# ISO_Power.net
KiCad netlist of a schematic drawn in Altium Designer
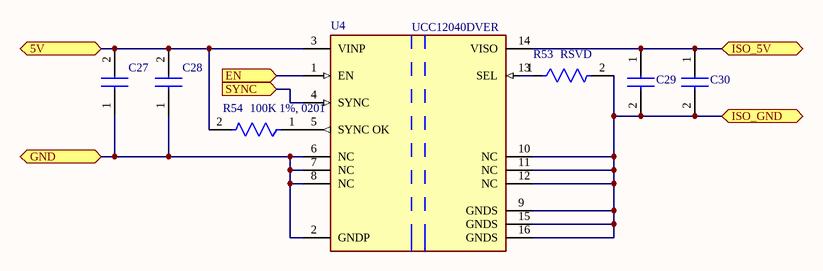
[diagram p0: ISO_Power.SchDoc]

(export (version "E")
  (design (tool "Eeschema 10.0.6"))
  (components
    (comp (ref "C27")
      (value "10 uF, 25V, X6S, 0402")
      (footprint "SamacSys:CAPC1005X70N")
      (description "Capacitor")
      (fields
        (field (name "MANUFACTURER_PART_NUMBER") "GRM155F51E104ZA01E")
        (field (name "MOUSER PART NUMBER") "81-GRM15F51E104ZA01E")
      )
      (libsource (lib "*") (part "GRM155F51E104ZA01E"))
    )
    (comp (ref "C28")
      (value "100 nF, 25V, X6S, 0201")
      (footprint "SamacSys:CAPC0603X33N")
      (description "Capacitor")
      (fields
        (field (name "MANUFACTURER_PART_NUMBER") "GRM033C81E104KE14D")
        (field (name "MOUSER PART NUMBER") "81-GRM33C81E104KE14D")
      )
      (libsource (lib "*") (part "GRM033C81E104KE14D"))
    )
    (comp (ref "C29")
      (value "100 nF, 25V, X6S, 0201")
      (footprint "SamacSys:CAPC0603X33N")
      (description "Capacitor")
      (fields
        (field (name "MANUFACTURER_PART_NUMBER") "GRM033C81E104KE14D")
        (field (name "MOUSER PART NUMBER") "81-GRM33C81E104KE14D")
      )
      (libsource (lib "*") (part "GRM033C81E104KE14D"))
    )
    (comp (ref "C30")
      (value "10 uF, 25V, X6S, 0402")
      (footprint "SamacSys:CAPC1005X70N")
      (description "Capacitor")
      (fields
        (field (name "MANUFACTURER_PART_NUMBER") "GRM155F51E104ZA01E")
        (field (name "MOUSER PART NUMBER") "81-GRM15F51E104ZA01E")
      )
      (libsource (lib "*") (part "GRM155F51E104ZA01E"))
    )
    (comp (ref "R53")
      (value "RSVD")
      (footprint "FP-ERJ1GN-IPC_A")
      (description "RES SMD 100K OHM 1% 1/20W 0201")
      (fields (field (name "TOLERANCE") "1%"))
      (libsource (lib "Altium Content Vault") (part "1029c3af85768c4190bb7ad29bc67b5"))
    )
    (comp (ref "R54")
      (value "100K 1%, 0201")
      (footprint "FP-ERJ1GN-IPC_A")
      (description "RES SMD 100K OHM 1% 1/20W 0201")
      (fields (field (name "TOLERANCE") "1%"))
      (libsource (lib "Altium Content Vault") (part "1029c3af85768c4190bb7ad29bc67b5"))
    )
    (comp (ref "U4")
      (value "UCC12040DVER")
      (footprint "FP-DVE0016A-MFG")
      (description "DC DC CONVERTER 3.3V 5V 500MW")
      (libsource (lib "Altium Content Vault") (part "cf9dcfd4a8b3775ff5e4cba6f3e7206"))
    )
  )
  (nets
    (net (code "1") (name "/5V") (class "Default")
      (node (ref "C27") (pin "2") (pinfunction "2_2") (pintype "passive"))
      (node (ref "C28") (pin "2") (pinfunction "2_2") (pintype "passive"))
      (node (ref "R54") (pin "2") (pinfunction "2_2") (pintype "passive"))
      (node (ref "U4") (pin "3") (pinfunction "VINP_3") (pintype "power_in"))
    )
    (net (code "2") (name "/EN") (class "Default")
      (node (ref "U4") (pin "1") (pinfunction "EN_1") (pintype "input"))
    )
    (net (code "3") (name "/GND") (class "Default")
      (node (ref "C27") (pin "1") (pinfunction "1_1") (pintype "passive"))
      (node (ref "C28") (pin "1") (pinfunction "1_1") (pintype "passive"))
      (node (ref "U4") (pin "2") (pinfunction "GNDP_2") (pintype "power_in"))
      (node (ref "U4") (pin "6") (pinfunction "NC_6") (pintype "passive"))
      (node (ref "U4") (pin "7") (pinfunction "NC_7") (pintype "passive"))
      (node (ref "U4") (pin "8") (pinfunction "NC_8") (pintype "passive"))
    )
    (net (code "4") (name "/ISO_5V") (class "Default")
      (node (ref "C29") (pin "1") (pinfunction "1_1") (pintype "passive"))
      (node (ref "C30") (pin "1") (pinfunction "1_1") (pintype "passive"))
      (node (ref "U4") (pin "14") (pinfunction "VISO_14") (pintype "power_in"))
    )
    (net (code "5") (name "/ISO_GND") (class "Default")
      (node (ref "C29") (pin "2") (pinfunction "2_2") (pintype "passive"))
      (node (ref "C30") (pin "2") (pinfunction "2_2") (pintype "passive"))
      (node (ref "R53") (pin "2") (pinfunction "2_2") (pintype "passive"))
      (node (ref "U4") (pin "10") (pinfunction "NC_10") (pintype "passive"))
      (node (ref "U4") (pin "11") (pinfunction "NC_11") (pintype "passive"))
      (node (ref "U4") (pin "12") (pinfunction "NC_12") (pintype "passive"))
      (node (ref "U4") (pin "15") (pinfunction "GNDS_15") (pintype "power_in"))
      (node (ref "U4") (pin "16") (pinfunction "GNDS_16") (pintype "power_in"))
      (node (ref "U4") (pin "9") (pinfunction "GNDS_9") (pintype "power_in"))
    )
    (net (code "6") (name "/SYNC") (class "Default")
      (node (ref "U4") (pin "4") (pinfunction "SYNC_4") (pintype "input"))
    )
    (net (code "7") (name "Net-(U4-SEL)") (class "Default")
      (node (ref "R53") (pin "1") (pinfunction "1_1") (pintype "passive"))
      (node (ref "U4") (pin "13") (pinfunction "SEL_13") (pintype "input"))
    )
    (net (code "8") (name "Net-(U4-SYNC_OK)") (class "Default")
      (node (ref "R54") (pin "1") (pinfunction "1_1") (pintype "passive"))
      (node (ref "U4") (pin "5") (pinfunction "SYNC_OK_5") (pintype "output"))
    )
  )
)
